# Power_Supply.net
KiCad netlist of a schematic drawn in EAGLE
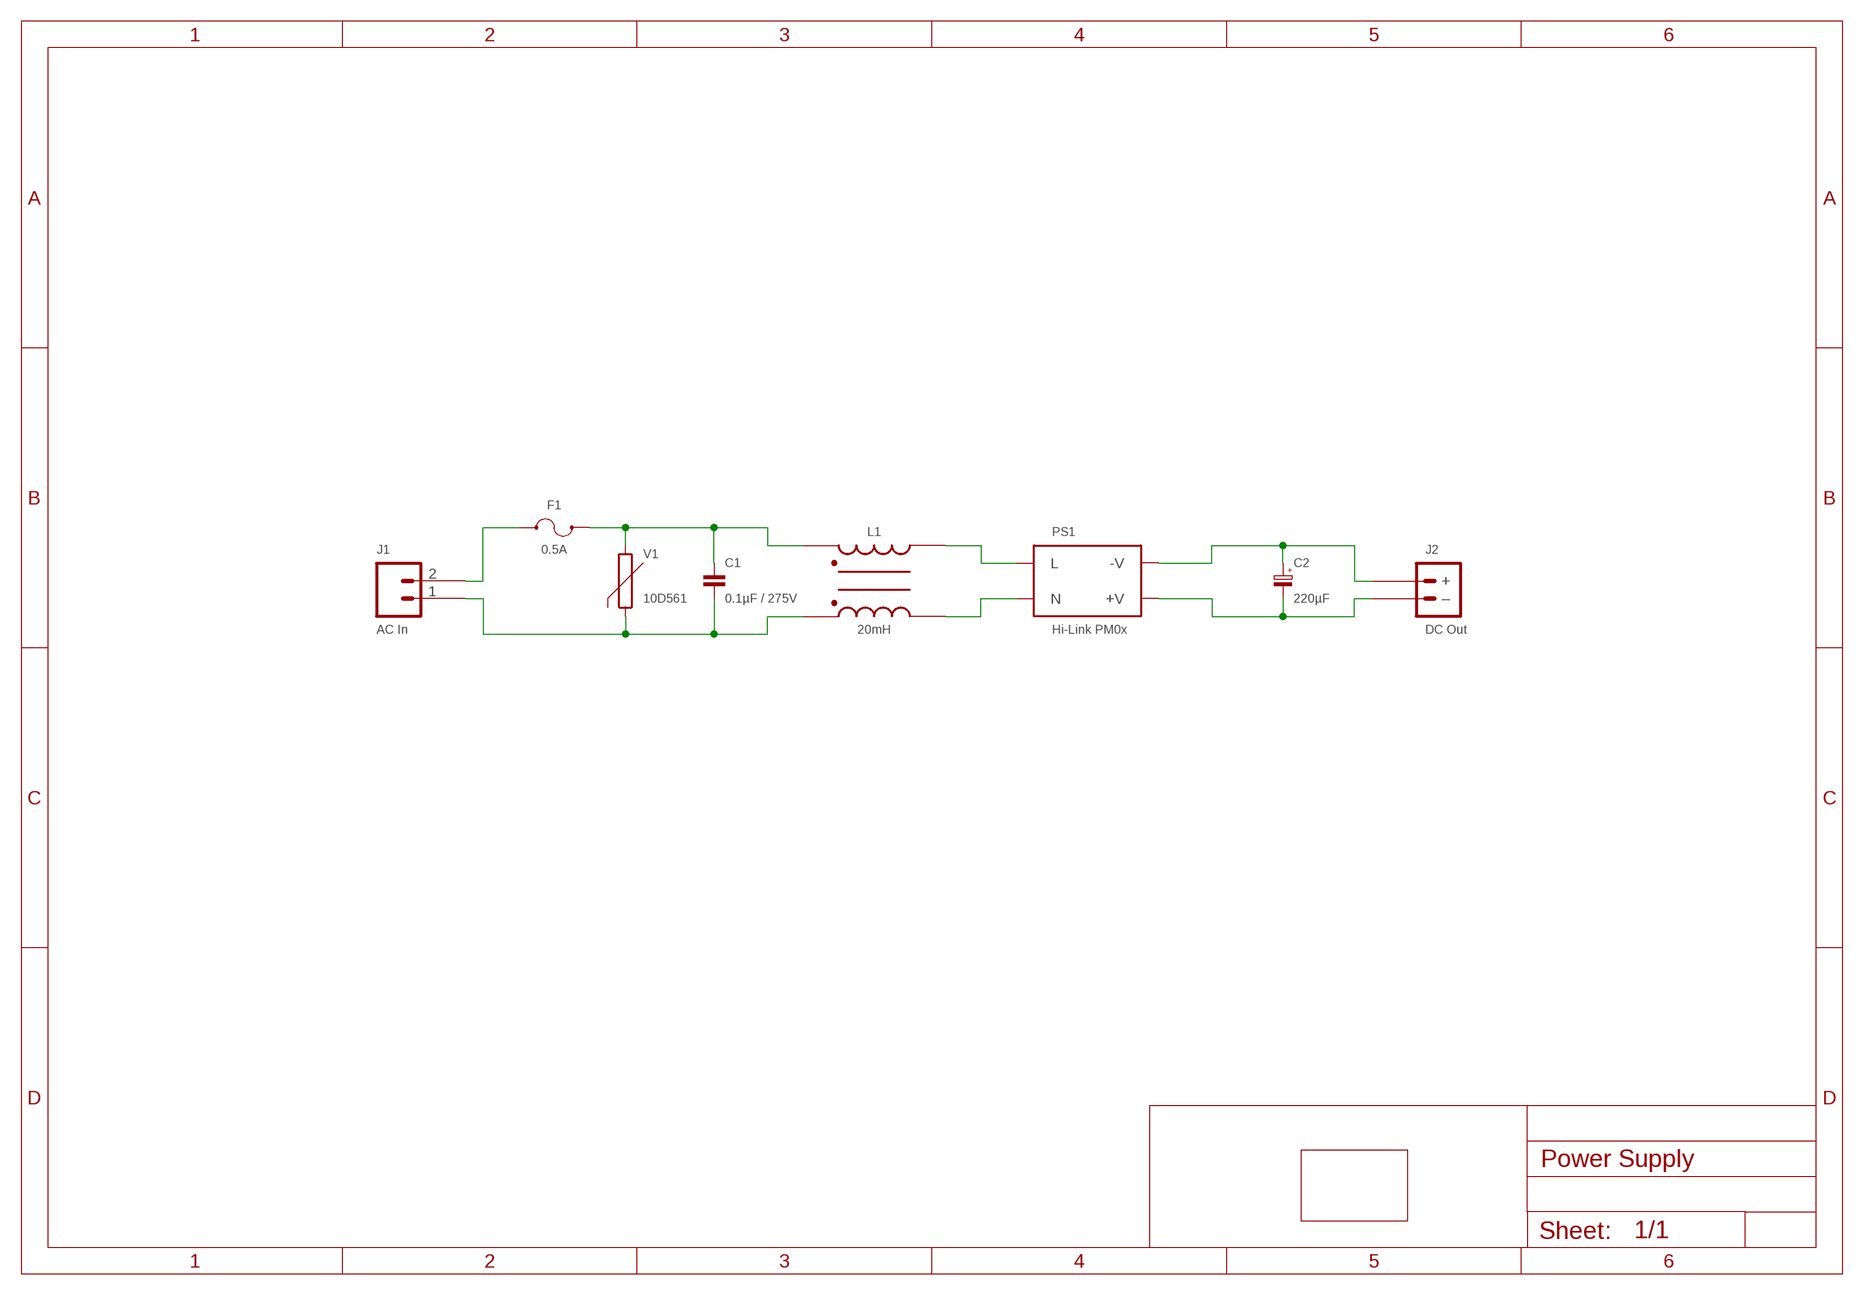
[diagram p0: schematic, sheet 1]

(export (version "E")
  (design (tool "Eeschema 10.0.6"))
  (components
    (comp (ref "C1")
      (value "0.1µF / 275V")
      (footprint "eagle-import:CAPACITOR-TENTA-SUPPRESSION")
      (libsource (lib "eagle-import") (part "CAPACITOR-TENTA-SUPPRESSION"))
    )
    (comp (ref "C2")
      (value "220µF")
      (footprint "eagle-import:E5-10,5")
      (libsource (lib "eagle-import") (part "CAPACITOR-ELECTROLYTICE5-10.5"))
    )
    (comp (ref "F1")
      (value "0.5A")
      (footprint "eagle-import:FUSE-HOLDER-1808")
      (libsource (lib "eagle-import") (part "FUSE-HOLDER-1808"))
    )
    (comp (ref "J1")
      (value "AC In")
      (footprint "eagle-import:JST-XH2.4-2-HORIZONTAL")
      (libsource (lib "eagle-import") (part "JST-XH2.54-2-HORIZONTAL"))
    )
    (comp (ref "J2")
      (value "DC Out")
      (footprint "eagle-import:JST-PH2.0-2-VERTICAL-POWER")
      (libsource (lib "eagle-import") (part "JST-PH2.0-2-VERTICAL-POWER"))
    )
    (comp (ref "L1")
      (value "20mH")
      (footprint "eagle-import:INDUCTOR-UU9.8")
      (libsource (lib "eagle-import") (part "INDUCTOR-COMMON-MODE-UU9.8"))
    )
    (comp (ref "PCB1")
      (value "PCB-OUTLINE-64X31")
      (footprint "eagle-import:PCB-POWER-SUPPLY")
      (libsource (lib "eagle-import") (part "PCB-OUTLINE-64X31"))
    )
    (comp (ref "PS1")
      (value "Hi-Link PM0x")
      (footprint "eagle-import:HI-LINK")
      (libsource (lib "eagle-import") (part "HI-LINK-POWER-SUPPLY"))
    )
    (comp (ref "V1")
      (value "10D561")
      (footprint "eagle-import:VARISTOR-10D561")
      (libsource (lib "eagle-import") (part "VARISTOR-10D561"))
    )
  )
  (nets
    (net (code "1") (name "Net-(C1-1)") (class "Default")
      (node (ref "C1") (pin "P$1") (pinfunction "1_P$1") (pintype "passive"))
      (node (ref "F1") (pin "P$2") (pinfunction "2_P$2") (pintype "passive"))
      (node (ref "L1") (pin "P$1") (pinfunction "1_P$1") (pintype "passive"))
      (node (ref "V1") (pin "2") (pinfunction "2_2") (pintype "passive"))
    )
    (net (code "2") (name "Net-(C1-2)") (class "Default")
      (node (ref "C1") (pin "P$2") (pinfunction "2_P$2") (pintype "passive"))
      (node (ref "J1") (pin "1") (pinfunction "1_1") (pintype "passive"))
      (node (ref "L1") (pin "P$4") (pinfunction "4_P$4") (pintype "passive"))
      (node (ref "V1") (pin "1") (pinfunction "1_1") (pintype "passive"))
    )
    (net (code "3") (name "Net-(F1-1)") (class "Default")
      (node (ref "F1") (pin "P$1") (pinfunction "1_P$1") (pintype "passive"))
      (node (ref "J1") (pin "2") (pinfunction "2_2") (pintype "passive"))
    )
    (net (code "4") (name "Net-(J2-–)") (class "Default")
      (node (ref "C2") (pin "-") (pinfunction "-_-") (pintype "passive"))
      (node (ref "J2") (pin "-") (pinfunction "–_-") (pintype "power_in"))
      (node (ref "PS1") (pin "+VO") (pinfunction "+V_+VO") (pintype "power_in"))
    )
    (net (code "5") (name "Net-(L1-2)") (class "Default")
      (node (ref "L1") (pin "P$2") (pinfunction "2_P$2") (pintype "passive"))
      (node (ref "PS1") (pin "AC-L") (pinfunction "L_AC-L") (pintype "power_in"))
    )
    (net (code "6") (name "Net-(L1-3)") (class "Default")
      (node (ref "L1") (pin "P$3") (pinfunction "3_P$3") (pintype "passive"))
      (node (ref "PS1") (pin "AC-N") (pinfunction "N_AC-N") (pintype "power_in"))
    )
    (net (code "7") (name "Net-(PS1--V)") (class "Default")
      (node (ref "C2") (pin "+") (pinfunction "+_+") (pintype "passive"))
      (node (ref "J2") (pin "+") (pinfunction "+_+") (pintype "power_in"))
      (node (ref "PS1") (pin "-VO") (pinfunction "-V_-VO") (pintype "power_in"))
    )
  )
)
